# project_vostok__tv_b_gone_extended__v1_1.net
KiCad netlist of a schematic drawn in EAGLE
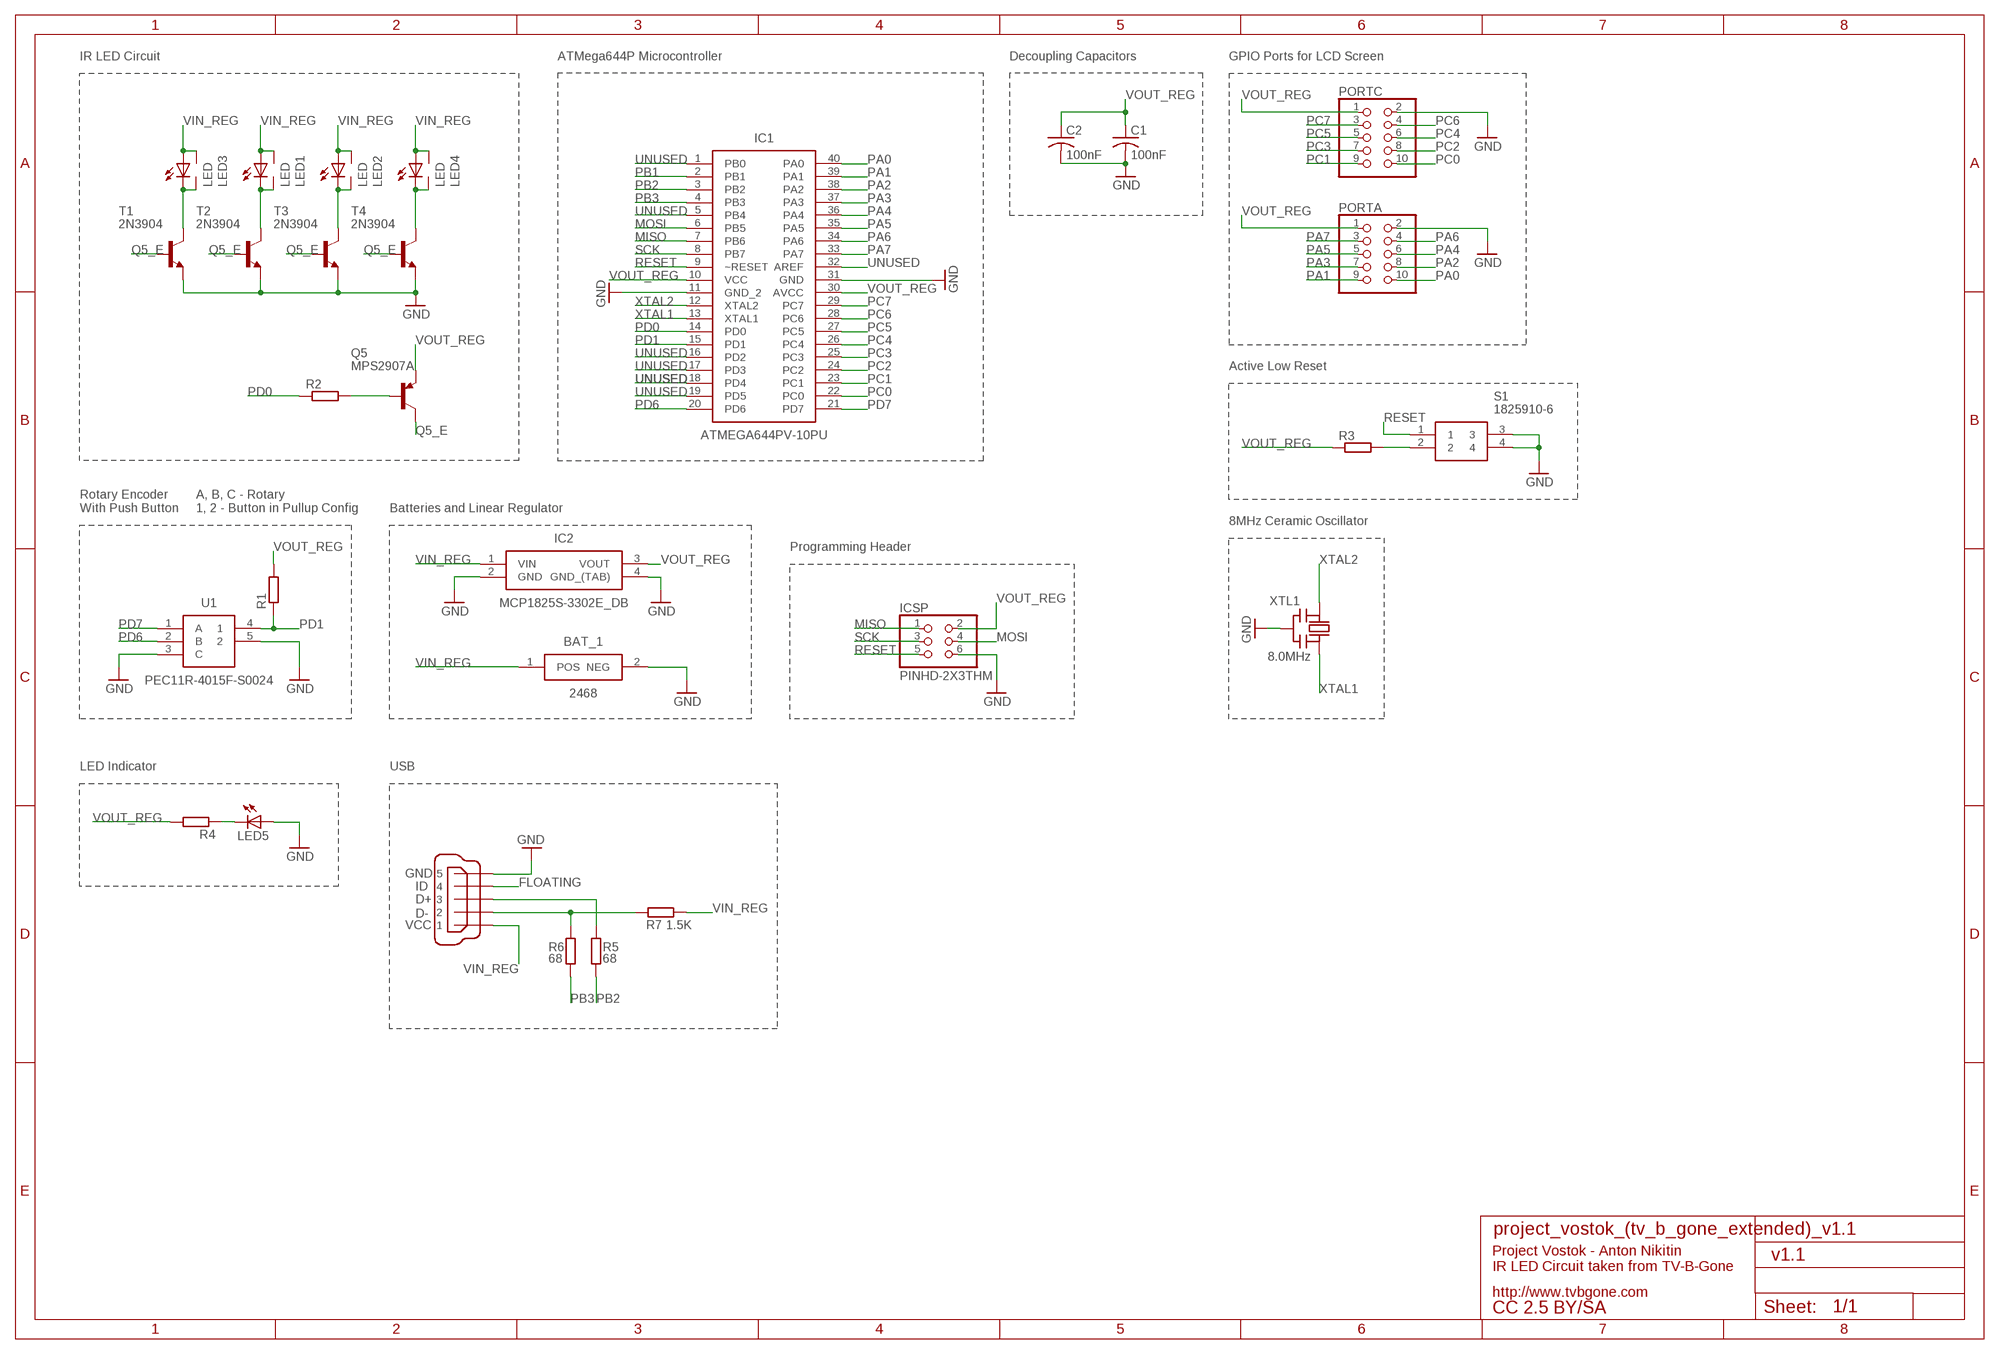
[diagram p0: schematic, sheet 1]

(export (version "E")
  (design (tool "Eeschema 10.0.6"))
  (components
    (comp (ref "BAT_1")
      (value "2468")
      (footprint "eagle-import:2468")
      (fields (field (name "RS_PART_NUMBER") "2794965"))
      (libsource (lib "eagle-import") (part "2468"))
    )
    (comp (ref "C1")
      (value "100nF")
      (footprint "eagle-import:C025-025X050")
      (libsource (lib "eagle-import") (part "C-US025-025X050"))
    )
    (comp (ref "C2")
      (value "100nF")
      (footprint "eagle-import:C025-025X050")
      (libsource (lib "eagle-import") (part "C-US025-025X050"))
    )
    (comp (ref "IC1")
      (value "ATMEGA644PV-10PU")
      (footprint "eagle-import:DIP254P1524X483-40")
      (fields (field (name "RS_PART_NUMBER") "7380491P"))
      (libsource (lib "eagle-import") (part "ATMEGA644PV-10PU"))
    )
    (comp (ref "IC2")
      (value "MCP1825S-3302E_DB")
      (footprint "eagle-import:SOT230P700X180-4N")
      (fields
        (field (name "MANUFACTURER_PART_NUMBER") "MCP1825S-3302E/DB")
        (field (name "RS_PART_NUMBER") "9115520")
      )
      (libsource (lib "eagle-import") (part "MCP1825S-3302E_DB"))
    )
    (comp (ref "ICSP")
      (value "PINHD-2X3THM")
      (footprint "eagle-import:ISP6")
      (libsource (lib "eagle-import") (part "PINHD-2X3THM"))
    )
    (comp (ref "LED1")
      (value "LED")
      (footprint "eagle-import:5MM-SIDE")
      (libsource (lib "eagle-import") (part "tvbgone_LED"))
    )
    (comp (ref "LED2")
      (value "LED")
      (footprint "eagle-import:5MM-SIDE")
      (libsource (lib "eagle-import") (part "tvbgone_LED"))
    )
    (comp (ref "LED3")
      (value "LED")
      (footprint "eagle-import:5MM-SIDE")
      (libsource (lib "eagle-import") (part "tvbgone_LED"))
    )
    (comp (ref "LED4")
      (value "LED")
      (footprint "eagle-import:5MM-SIDE")
      (libsource (lib "eagle-import") (part "tvbgone_LED"))
    )
    (comp (ref "LED5")
      (value "LED5MM")
      (footprint "eagle-import:LED5MM")
      (libsource (lib "eagle-import") (part "LED5MM"))
    )
    (comp (ref "PORTA")
      (value "PINHD-2X5")
      (footprint "eagle-import:2X05")
      (libsource (lib "eagle-import") (part "PINHD-2X5"))
    )
    (comp (ref "PORTC")
      (value "PINHD-2X5")
      (footprint "eagle-import:2X05")
      (libsource (lib "eagle-import") (part "PINHD-2X5"))
    )
    (comp (ref "Q5")
      (value "MPS2907A")
      (footprint "eagle-import:TO92-CBE")
      (libsource (lib "eagle-import") (part "MPS2907A"))
    )
    (comp (ref "R1")
      (value "R-EU_0204/7")
      (footprint "eagle-import:0204_7")
      (libsource (lib "eagle-import") (part "R-EU_0204/7"))
    )
    (comp (ref "R2")
      (value "R-EU_0204/7")
      (footprint "eagle-import:0204_7")
      (libsource (lib "eagle-import") (part "R-EU_0204/7"))
    )
    (comp (ref "R3")
      (value "R-EU_0204/7")
      (footprint "eagle-import:0204_7")
      (libsource (lib "eagle-import") (part "R-EU_0204/7"))
    )
    (comp (ref "R4")
      (value "R-EU_0204/7")
      (footprint "eagle-import:0204_7")
      (libsource (lib "eagle-import") (part "R-EU_0204/7"))
    )
    (comp (ref "R5")
      (value "68")
      (footprint "eagle-import:0204_7")
      (libsource (lib "eagle-import") (part "R-EU_0204/7"))
    )
    (comp (ref "R6")
      (value "68")
      (footprint "eagle-import:0204_7")
      (libsource (lib "eagle-import") (part "R-EU_0204/7"))
    )
    (comp (ref "R7")
      (value "1.5K")
      (footprint "eagle-import:0204_7")
      (libsource (lib "eagle-import") (part "R-EU_0204/7"))
    )
    (comp (ref "S1")
      (value "1825910-6")
      (footprint "eagle-import:1825910-6")
      (fields (field (name "RS_PART_NUMBER") "1613779"))
      (libsource (lib "eagle-import") (part "1825910-6"))
    )
    (comp (ref "T1")
      (value "2N3904")
      (footprint "eagle-import:TO92")
      (libsource (lib "eagle-import") (part "2N3904"))
    )
    (comp (ref "T2")
      (value "2N3904")
      (footprint "eagle-import:TO92")
      (libsource (lib "eagle-import") (part "2N3904"))
    )
    (comp (ref "T3")
      (value "2N3904")
      (footprint "eagle-import:TO92")
      (libsource (lib "eagle-import") (part "2N3904"))
    )
    (comp (ref "T4")
      (value "2N3904")
      (footprint "eagle-import:TO92")
      (libsource (lib "eagle-import") (part "2N3904"))
    )
    (comp (ref "U1")
      (value "PEC11R-4015F-S0024")
      (footprint "eagle-import:PEC12R-4XXXF-SXXXX_1")
      (fields (field (name "RS_PART_NUMBER") "7377739P"))
      (libsource (lib "eagle-import") (part "PEC11R-4015F-S0024"))
    )
    (comp (ref "X1")
      (value "MINI-USB_SHIELD5P2-32005-601")
      (footprint "eagle-import:32005-601")
      (libsource (lib "eagle-import") (part "MINI-USB_SHIELD5P2-32005-601"))
    )
    (comp (ref "XTL1")
      (value "8.0MHz")
      (footprint "eagle-import:CERM_OSC")
      (libsource (lib "eagle-import") (part "CERMOSCILL"))
    )
  )
  (nets
    (net (code "1") (name "/MISO") (class "Default")
      (node (ref "IC1") (pin "7") (pinfunction "PB6_7") (pintype "passive"))
      (node (ref "ICSP") (pin "1") (pinfunction "1_1") (pintype "passive"))
    )
    (net (code "2") (name "/MOSI") (class "Default")
      (node (ref "IC1") (pin "6") (pinfunction "PB5_6") (pintype "passive"))
      (node (ref "ICSP") (pin "4") (pinfunction "4_4") (pintype "passive"))
    )
    (net (code "3") (name "/PA0") (class "Default")
      (node (ref "IC1") (pin "40") (pinfunction "PA0_40") (pintype "passive"))
      (node (ref "PORTA") (pin "10") (pinfunction "10_10") (pintype "passive"))
    )
    (net (code "4") (name "/PA1") (class "Default")
      (node (ref "IC1") (pin "39") (pinfunction "PA1_39") (pintype "passive"))
      (node (ref "PORTA") (pin "9") (pinfunction "9_9") (pintype "passive"))
    )
    (net (code "5") (name "/PA2") (class "Default")
      (node (ref "IC1") (pin "38") (pinfunction "PA2_38") (pintype "passive"))
      (node (ref "PORTA") (pin "8") (pinfunction "8_8") (pintype "passive"))
    )
    (net (code "6") (name "/PA3") (class "Default")
      (node (ref "IC1") (pin "37") (pinfunction "PA3_37") (pintype "passive"))
      (node (ref "PORTA") (pin "7") (pinfunction "7_7") (pintype "passive"))
    )
    (net (code "7") (name "/PA4") (class "Default")
      (node (ref "IC1") (pin "36") (pinfunction "PA4_36") (pintype "passive"))
      (node (ref "PORTA") (pin "6") (pinfunction "6_6") (pintype "passive"))
    )
    (net (code "8") (name "/PA5") (class "Default")
      (node (ref "IC1") (pin "35") (pinfunction "PA5_35") (pintype "passive"))
      (node (ref "PORTA") (pin "5") (pinfunction "5_5") (pintype "passive"))
    )
    (net (code "9") (name "/PA6") (class "Default")
      (node (ref "IC1") (pin "34") (pinfunction "PA6_34") (pintype "passive"))
      (node (ref "PORTA") (pin "4") (pinfunction "4_4") (pintype "passive"))
    )
    (net (code "10") (name "/PA7") (class "Default")
      (node (ref "IC1") (pin "33") (pinfunction "PA7_33") (pintype "passive"))
      (node (ref "PORTA") (pin "3") (pinfunction "3_3") (pintype "passive"))
    )
    (net (code "11") (name "/PB2") (class "Default")
      (node (ref "IC1") (pin "3") (pinfunction "PB2_3") (pintype "passive"))
      (node (ref "R5") (pin "2") (pinfunction "2_2") (pintype "passive"))
    )
    (net (code "12") (name "/PB3") (class "Default")
      (node (ref "IC1") (pin "4") (pinfunction "PB3_4") (pintype "passive"))
      (node (ref "R6") (pin "2") (pinfunction "2_2") (pintype "passive"))
    )
    (net (code "13") (name "/PC0") (class "Default")
      (node (ref "IC1") (pin "22") (pinfunction "PC0_22") (pintype "passive"))
      (node (ref "PORTC") (pin "10") (pinfunction "10_10") (pintype "passive"))
    )
    (net (code "14") (name "/PC1") (class "Default")
      (node (ref "IC1") (pin "23") (pinfunction "PC1_23") (pintype "passive"))
      (node (ref "PORTC") (pin "9") (pinfunction "9_9") (pintype "passive"))
    )
    (net (code "15") (name "/PC2") (class "Default")
      (node (ref "IC1") (pin "24") (pinfunction "PC2_24") (pintype "passive"))
      (node (ref "PORTC") (pin "8") (pinfunction "8_8") (pintype "passive"))
    )
    (net (code "16") (name "/PC3") (class "Default")
      (node (ref "IC1") (pin "25") (pinfunction "PC3_25") (pintype "passive"))
      (node (ref "PORTC") (pin "7") (pinfunction "7_7") (pintype "passive"))
    )
    (net (code "17") (name "/PC4") (class "Default")
      (node (ref "IC1") (pin "26") (pinfunction "PC4_26") (pintype "passive"))
      (node (ref "PORTC") (pin "6") (pinfunction "6_6") (pintype "passive"))
    )
    (net (code "18") (name "/PC5") (class "Default")
      (node (ref "IC1") (pin "27") (pinfunction "PC5_27") (pintype "passive"))
      (node (ref "PORTC") (pin "5") (pinfunction "5_5") (pintype "passive"))
    )
    (net (code "19") (name "/PC6") (class "Default")
      (node (ref "IC1") (pin "28") (pinfunction "PC6_28") (pintype "passive"))
      (node (ref "PORTC") (pin "4") (pinfunction "4_4") (pintype "passive"))
    )
    (net (code "20") (name "/PC7") (class "Default")
      (node (ref "IC1") (pin "29") (pinfunction "PC7_29") (pintype "passive"))
      (node (ref "PORTC") (pin "3") (pinfunction "3_3") (pintype "passive"))
    )
    (net (code "21") (name "/PD0") (class "Default")
      (node (ref "IC1") (pin "14") (pinfunction "PD0_14") (pintype "passive"))
      (node (ref "R2") (pin "1") (pinfunction "1_1") (pintype "passive"))
    )
    (net (code "22") (name "/PD1") (class "Default")
      (node (ref "IC1") (pin "15") (pinfunction "PD1_15") (pintype "passive"))
      (node (ref "R1") (pin "1") (pinfunction "1_1") (pintype "passive"))
      (node (ref "U1") (pin "4") (pinfunction "1_4") (pintype "passive"))
    )
    (net (code "23") (name "/PD6") (class "Default")
      (node (ref "IC1") (pin "20") (pinfunction "PD6_20") (pintype "passive"))
      (node (ref "U1") (pin "2") (pinfunction "B_2") (pintype "passive"))
    )
    (net (code "24") (name "/PD7") (class "Default")
      (node (ref "IC1") (pin "21") (pinfunction "PD7_21") (pintype "passive"))
      (node (ref "U1") (pin "1") (pinfunction "A_1") (pintype "passive"))
    )
    (net (code "25") (name "/Q5_E") (class "Default")
      (node (ref "Q5") (pin "C") (pinfunction "C_C") (pintype "passive"))
      (node (ref "T1") (pin "2") (pinfunction "B_2") (pintype "passive"))
      (node (ref "T2") (pin "2") (pinfunction "B_2") (pintype "passive"))
      (node (ref "T3") (pin "2") (pinfunction "B_2") (pintype "passive"))
      (node (ref "T4") (pin "2") (pinfunction "B_2") (pintype "passive"))
    )
    (net (code "26") (name "/RESET") (class "Default")
      (node (ref "IC1") (pin "9") (pinfunction "~{RESET}_9") (pintype "passive"))
      (node (ref "ICSP") (pin "5") (pinfunction "5_5") (pintype "passive"))
      (node (ref "S1") (pin "1") (pinfunction "1_1") (pintype "input"))
    )
    (net (code "27") (name "/SCK") (class "Default")
      (node (ref "IC1") (pin "8") (pinfunction "PB7_8") (pintype "passive"))
      (node (ref "ICSP") (pin "3") (pinfunction "3_3") (pintype "passive"))
    )
    (net (code "28") (name "/VIN_REG") (class "Default")
      (node (ref "BAT_1") (pin "1") (pinfunction "POS_1") (pintype "passive"))
      (node (ref "IC2") (pin "1") (pinfunction "VIN_1") (pintype "input"))
      (node (ref "LED1") (pin "A") (pinfunction "A_A") (pintype "passive"))
      (node (ref "LED1") (pin "A2") (pinfunction "A1_A2") (pintype "passive"))
      (node (ref "LED2") (pin "A") (pinfunction "A_A") (pintype "passive"))
      (node (ref "LED2") (pin "A2") (pinfunction "A1_A2") (pintype "passive"))
      (node (ref "LED3") (pin "A") (pinfunction "A_A") (pintype "passive"))
      (node (ref "LED3") (pin "A2") (pinfunction "A1_A2") (pintype "passive"))
      (node (ref "LED4") (pin "A") (pinfunction "A_A") (pintype "passive"))
      (node (ref "LED4") (pin "A2") (pinfunction "A1_A2") (pintype "passive"))
      (node (ref "R7") (pin "2") (pinfunction "2_2") (pintype "passive"))
      (node (ref "X1") (pin "1") (pinfunction "1_1") (pintype "passive"))
    )
    (net (code "29") (name "/VOUT_REG") (class "Default")
      (node (ref "C1") (pin "1") (pinfunction "1_1") (pintype "passive"))
      (node (ref "C2") (pin "1") (pinfunction "1_1") (pintype "passive"))
      (node (ref "IC1") (pin "10") (pinfunction "VCC_10") (pintype "passive"))
      (node (ref "IC1") (pin "30") (pinfunction "AVCC_30") (pintype "passive"))
      (node (ref "IC2") (pin "3") (pinfunction "VOUT_3") (pintype "output"))
      (node (ref "ICSP") (pin "2") (pinfunction "2_2") (pintype "passive"))
      (node (ref "PORTA") (pin "1") (pinfunction "1_1") (pintype "passive"))
      (node (ref "PORTC") (pin "1") (pinfunction "1_1") (pintype "passive"))
      (node (ref "Q5") (pin "E") (pinfunction "E_E") (pintype "passive"))
      (node (ref "R1") (pin "2") (pinfunction "2_2") (pintype "passive"))
      (node (ref "R3") (pin "1") (pinfunction "1_1") (pintype "passive"))
      (node (ref "R4") (pin "2") (pinfunction "2_2") (pintype "passive"))
    )
    (net (code "30") (name "/XTAL1") (class "Default")
      (node (ref "IC1") (pin "13") (pinfunction "XTAL1_13") (pintype "passive"))
      (node (ref "XTL1") (pin "P$3") (pinfunction "OUT_P$3") (pintype "bidirectional"))
    )
    (net (code "31") (name "/XTAL2") (class "Default")
      (node (ref "IC1") (pin "12") (pinfunction "XTAL2_12") (pintype "passive"))
      (node (ref "XTL1") (pin "P$1") (pinfunction "IN_P$1") (pintype "bidirectional"))
    )
    (net (code "32") (name "GND") (class "Default")
      (node (ref "BAT_1") (pin "2") (pinfunction "NEG_2") (pintype "passive"))
      (node (ref "C1") (pin "2") (pinfunction "2_2") (pintype "passive"))
      (node (ref "C2") (pin "2") (pinfunction "2_2") (pintype "passive"))
      (node (ref "IC1") (pin "11") (pinfunction "GND_2_11") (pintype "passive"))
      (node (ref "IC1") (pin "31") (pinfunction "GND_31") (pintype "passive"))
      (node (ref "IC2") (pin "2") (pinfunction "GND_2") (pintype "power_in"))
      (node (ref "IC2") (pin "4") (pinfunction "GND_(TAB)_4") (pintype "power_in"))
      (node (ref "ICSP") (pin "6") (pinfunction "6_6") (pintype "passive"))
      (node (ref "LED5") (pin "A") (pinfunction "A_A") (pintype "passive"))
      (node (ref "PORTA") (pin "2") (pinfunction "2_2") (pintype "passive"))
      (node (ref "PORTC") (pin "2") (pinfunction "2_2") (pintype "passive"))
      (node (ref "S1") (pin "3") (pinfunction "3_3") (pintype "input"))
      (node (ref "S1") (pin "4") (pinfunction "4_4") (pintype "input"))
      (node (ref "T1") (pin "3") (pinfunction "E_3") (pintype "passive"))
      (node (ref "T2") (pin "3") (pinfunction "E_3") (pintype "passive"))
      (node (ref "T3") (pin "3") (pinfunction "E_3") (pintype "passive"))
      (node (ref "T4") (pin "3") (pinfunction "E_3") (pintype "passive"))
      (node (ref "U1") (pin "3") (pinfunction "C_3") (pintype "passive"))
      (node (ref "U1") (pin "5") (pinfunction "2_5") (pintype "passive"))
      (node (ref "X1") (pin "5") (pinfunction "5_5") (pintype "passive"))
      (node (ref "XTL1") (pin "P$2") (pinfunction "GND_P$2") (pintype "bidirectional"))
    )
    (net (code "33") (name "Net-(LED1-C)") (class "Default")
      (node (ref "LED1") (pin "K") (pinfunction "C_K") (pintype "passive"))
      (node (ref "LED1") (pin "K2") (pinfunction "C1_K2") (pintype "passive"))
      (node (ref "T2") (pin "1") (pinfunction "C_1") (pintype "passive"))
    )
    (net (code "34") (name "Net-(LED2-C)") (class "Default")
      (node (ref "LED2") (pin "K") (pinfunction "C_K") (pintype "passive"))
      (node (ref "LED2") (pin "K2") (pinfunction "C1_K2") (pintype "passive"))
      (node (ref "T3") (pin "1") (pinfunction "C_1") (pintype "passive"))
    )
    (net (code "35") (name "Net-(LED3-C)") (class "Default")
      (node (ref "LED3") (pin "K") (pinfunction "C_K") (pintype "passive"))
      (node (ref "LED3") (pin "K2") (pinfunction "C1_K2") (pintype "passive"))
      (node (ref "T1") (pin "1") (pinfunction "C_1") (pintype "passive"))
    )
    (net (code "36") (name "Net-(LED4-C)") (class "Default")
      (node (ref "LED4") (pin "K") (pinfunction "C_K") (pintype "passive"))
      (node (ref "LED4") (pin "K2") (pinfunction "C1_K2") (pintype "passive"))
      (node (ref "T4") (pin "1") (pinfunction "C_1") (pintype "passive"))
    )
    (net (code "37") (name "Net-(LED5-C)") (class "Default")
      (node (ref "LED5") (pin "K") (pinfunction "C_K") (pintype "passive"))
      (node (ref "R4") (pin "1") (pinfunction "1_1") (pintype "passive"))
    )
    (net (code "38") (name "Net-(Q5-PadB)") (class "Default")
      (node (ref "Q5") (pin "B") (pinfunction "B_B") (pintype "passive"))
      (node (ref "R2") (pin "2") (pinfunction "2_2") (pintype "passive"))
    )
    (net (code "39") (name "Net-(R3-Pad2)") (class "Default")
      (node (ref "R3") (pin "2") (pinfunction "2_2") (pintype "passive"))
      (node (ref "S1") (pin "2") (pinfunction "2_2") (pintype "input"))
    )
    (net (code "40") (name "Net-(R5-Pad1)") (class "Default")
      (node (ref "R5") (pin "1") (pinfunction "1_1") (pintype "passive"))
      (node (ref "X1") (pin "3") (pinfunction "3_3") (pintype "passive"))
    )
    (net (code "41") (name "Net-(R6-Pad1)") (class "Default")
      (node (ref "R6") (pin "1") (pinfunction "1_1") (pintype "passive"))
      (node (ref "R7") (pin "1") (pinfunction "1_1") (pintype "passive"))
      (node (ref "X1") (pin "2") (pinfunction "2_2") (pintype "passive"))
    )
    (net (code "42") (name "unconnected-(IC1-AREF-Pad32)") (class "Default")
      (node (ref "IC1") (pin "32") (pinfunction "AREF_32") (pintype "passive"))
    )
    (net (code "43") (name "unconnected-(IC1-PB0-Pad1)") (class "Default")
      (node (ref "IC1") (pin "1") (pinfunction "PB0_1") (pintype "passive"))
    )
    (net (code "44") (name "unconnected-(IC1-PB1-Pad2)") (class "Default")
      (node (ref "IC1") (pin "2") (pinfunction "PB1_2") (pintype "passive"))
    )
    (net (code "45") (name "unconnected-(IC1-PB4-Pad5)") (class "Default")
      (node (ref "IC1") (pin "5") (pinfunction "PB4_5") (pintype "passive"))
    )
    (net (code "46") (name "unconnected-(IC1-PD2-Pad16)") (class "Default")
      (node (ref "IC1") (pin "16") (pinfunction "PD2_16") (pintype "passive"))
    )
    (net (code "47") (name "unconnected-(IC1-PD3-Pad17)") (class "Default")
      (node (ref "IC1") (pin "17") (pinfunction "PD3_17") (pintype "passive"))
    )
    (net (code "48") (name "unconnected-(IC1-PD4-Pad18)") (class "Default")
      (node (ref "IC1") (pin "18") (pinfunction "PD4_18") (pintype "passive"))
    )
    (net (code "49") (name "unconnected-(IC1-PD5-Pad19)") (class "Default")
      (node (ref "IC1") (pin "19") (pinfunction "PD5_19") (pintype "passive"))
    )
    (net (code "50") (name "unconnected-(X1-Pad4)") (class "Default")
      (node (ref "X1") (pin "4") (pinfunction "4_4") (pintype "passive"))
    )
  )
)
